# 14_HD4_PUMP.net
KiCad netlist of a schematic drawn in Altium Designer
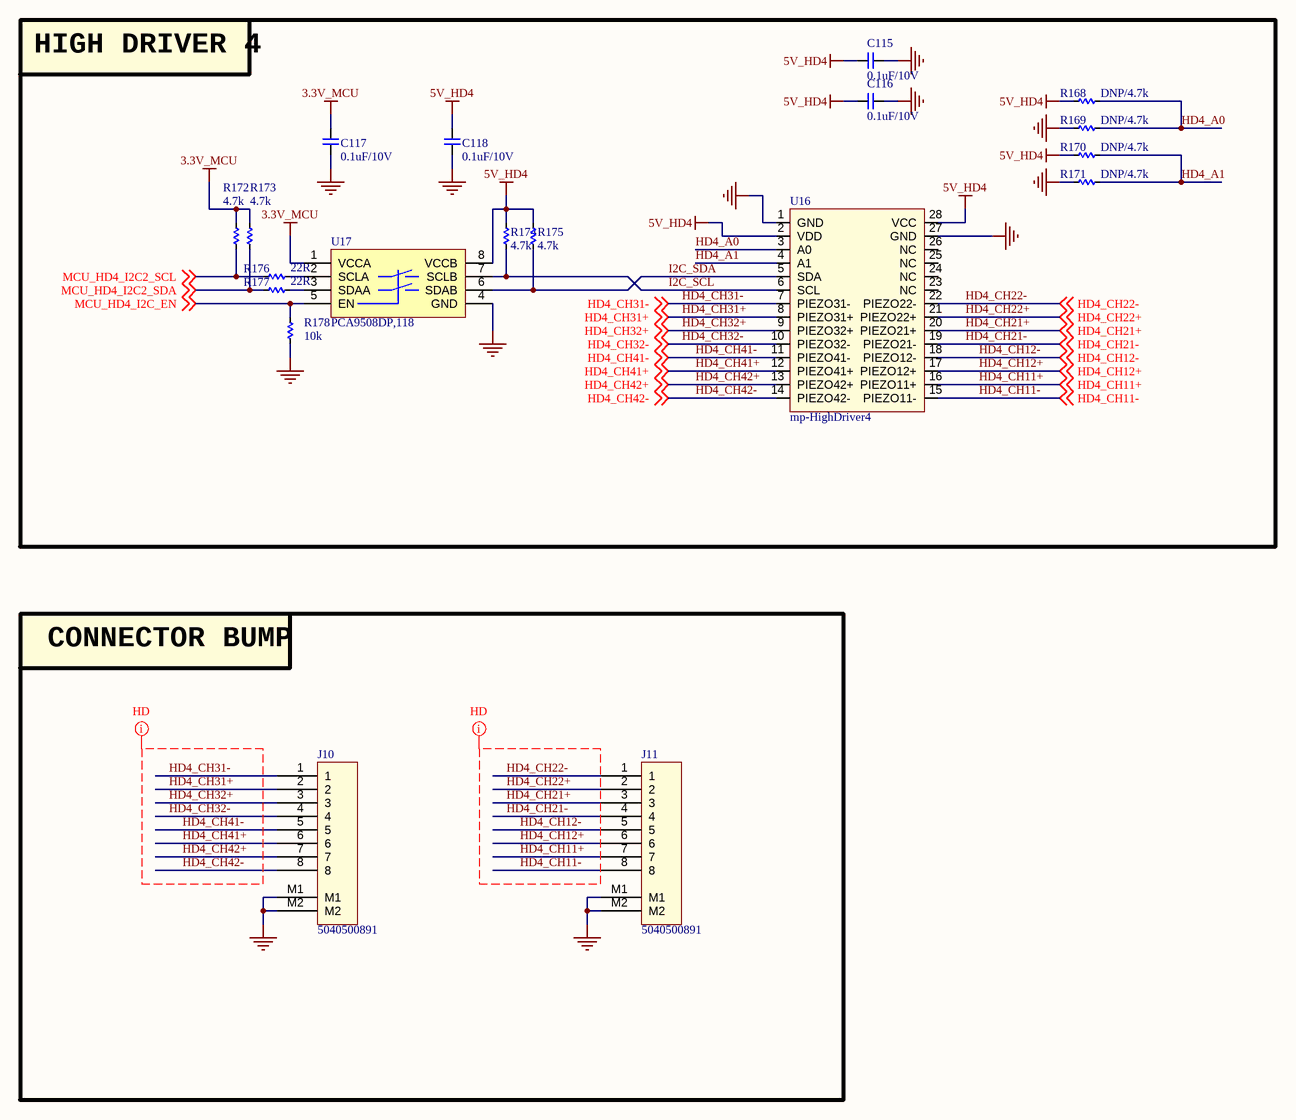
[diagram p0: 14_HD4_PUMP.SchDoc]

(export (version "E")
  (design (tool "Eeschema 10.0.6"))
  (components
    (comp (ref "C115")
      (value "0.1uF/10V")
      (footprint "CAP_C_1005X60")
      (description "CAP CHIP")
      (libsource (lib "LABLIB") (part "_CAP_C_2"))
    )
    (comp (ref "C116")
      (value "0.1uF/10V")
      (footprint "CAP_C_1005X60")
      (description "CAP CHIP")
      (libsource (lib "LABLIB") (part "_CAP_C_2"))
    )
    (comp (ref "C117")
      (value "0.1uF/10V")
      (footprint "CAP_C_1005X60")
      (description "CAP CHIP")
      (libsource (lib "LABLIB") (part "_CAP_C_2"))
    )
    (comp (ref "C118")
      (value "0.1uF/10V")
      (footprint "CAP_C_1005X60")
      (description "CAP CHIP")
      (libsource (lib "LABLIB") (part "_CAP_C_2"))
    )
    (comp (ref "J10")
      (value "5040500891")
      (footprint "MOLEX_5040500891")
      (libsource (lib "LABLIB") (part "Header 8x1_2M"))
    )
    (comp (ref "J11")
      (value "5040500891")
      (footprint "MOLEX_5040500891")
      (libsource (lib "LABLIB") (part "Header 8x1_2M"))
    )
    (comp (ref "R168")
      (value "DNP/4.7k")
      (footprint "RES_C_1005X40")
      (description "RES")
      (libsource (lib "LABLIB") (part "_RES_B_2"))
    )
    (comp (ref "R169")
      (value "DNP/4.7k")
      (footprint "RES_C_1005X40")
      (description "RES")
      (libsource (lib "LABLIB") (part "_RES_B_2"))
    )
    (comp (ref "R170")
      (value "DNP/4.7k")
      (footprint "RES_C_1005X40")
      (description "RES")
      (libsource (lib "LABLIB") (part "_RES_B_2"))
    )
    (comp (ref "R171")
      (value "DNP/4.7k")
      (footprint "RES_C_1005X40")
      (description "RES")
      (libsource (lib "LABLIB") (part "_RES_B_2"))
    )
    (comp (ref "R172")
      (value "4.7k")
      (footprint "RES_C_1005X40")
      (description "RES")
      (libsource (lib "LABLIB") (part "_RES_B_2"))
    )
    (comp (ref "R173")
      (value "4.7k")
      (footprint "RES_C_1005X40")
      (description "RES")
      (libsource (lib "LABLIB") (part "_RES_B_2"))
    )
    (comp (ref "R174")
      (value "4.7k")
      (footprint "RES_C_1005X40")
      (description "RES")
      (libsource (lib "LABLIB") (part "_RES_B_2"))
    )
    (comp (ref "R175")
      (value "4.7k")
      (footprint "RES_C_1005X40")
      (description "RES")
      (libsource (lib "LABLIB") (part "_RES_B_2"))
    )
    (comp (ref "R176")
      (value "22R")
      (footprint "RES_C_1005X40")
      (description "RES")
      (libsource (lib "LABLIB") (part "_RES_B_2"))
    )
    (comp (ref "R177")
      (value "22R")
      (footprint "RES_C_1005X40")
      (description "RES")
      (libsource (lib "LABLIB") (part "_RES_B_2"))
    )
    (comp (ref "R178")
      (value "10k")
      (footprint "RES_C_1005X40")
      (description "RES")
      (libsource (lib "LABLIB") (part "_RES_B_2"))
    )
    (comp (ref "U16")
      (value "mp-HighDriver4")
      (footprint "MP_HIGHDRIVER4")
      (libsource (lib "new_component") (part "mp_HighDriver4"))
    )
    (comp (ref "U17")
      (value "PCA9508DP,118")
      (footprint "TSOP8")
      (libsource (lib "EXP_HW_V3") (part "PCA9508DP,118"))
    )
  )
  (nets
    (net (code "1") (name "/HD4_A0") (class "Default")
      (node (ref "R168") (pin "2") (pinfunction "2_2") (pintype "passive"))
      (node (ref "R169") (pin "2") (pinfunction "2_2") (pintype "passive"))
      (node (ref "U16") (pin "3") (pinfunction "A0_3") (pintype "passive"))
    )
    (net (code "2") (name "/HD4_A1") (class "Default")
      (node (ref "R170") (pin "2") (pinfunction "2_2") (pintype "passive"))
      (node (ref "R171") (pin "2") (pinfunction "2_2") (pintype "passive"))
      (node (ref "U16") (pin "4") (pinfunction "A1_4") (pintype "passive"))
    )
    (net (code "3") (name "/I2C_SCL") (class "Default")
      (node (ref "R174") (pin "2") (pinfunction "2_2") (pintype "passive"))
      (node (ref "U16") (pin "6") (pinfunction "SCL_6") (pintype "passive"))
      (node (ref "U17") (pin "7") (pinfunction "SCLB_7") (pintype "passive"))
    )
    (net (code "4") (name "/I2C_SDA") (class "Default")
      (node (ref "R175") (pin "2") (pinfunction "2_2") (pintype "passive"))
      (node (ref "U16") (pin "5") (pinfunction "SDA_5") (pintype "passive"))
      (node (ref "U17") (pin "6") (pinfunction "SDAB_6") (pintype "passive"))
    )
    (net (code "5") (name "3.3V_MCU") (class "Default")
      (node (ref "C117") (pin "2") (pinfunction "2_2") (pintype "passive"))
      (node (ref "R172") (pin "1") (pinfunction "1_1") (pintype "passive"))
      (node (ref "R173") (pin "1") (pinfunction "1_1") (pintype "passive"))
      (node (ref "U17") (pin "1") (pinfunction "VCCA_1") (pintype "passive"))
    )
    (net (code "6") (name "5V_HD4") (class "Default")
      (node (ref "C115") (pin "2") (pinfunction "2_2") (pintype "passive"))
      (node (ref "C116") (pin "2") (pinfunction "2_2") (pintype "passive"))
      (node (ref "C118") (pin "2") (pinfunction "2_2") (pintype "passive"))
      (node (ref "R168") (pin "1") (pinfunction "1_1") (pintype "passive"))
      (node (ref "R170") (pin "1") (pinfunction "1_1") (pintype "passive"))
      (node (ref "R174") (pin "1") (pinfunction "1_1") (pintype "passive"))
      (node (ref "R175") (pin "1") (pinfunction "1_1") (pintype "passive"))
      (node (ref "U16") (pin "2") (pinfunction "VDD_2") (pintype "power_in"))
      (node (ref "U16") (pin "28") (pinfunction "VCC_28") (pintype "power_in"))
      (node (ref "U17") (pin "8") (pinfunction "VCCB_8") (pintype "passive"))
    )
    (net (code "7") (name "GND") (class "Default")
      (node (ref "C115") (pin "1") (pinfunction "1_1") (pintype "passive"))
      (node (ref "C116") (pin "1") (pinfunction "1_1") (pintype "passive"))
      (node (ref "C117") (pin "1") (pinfunction "1_1") (pintype "passive"))
      (node (ref "C118") (pin "1") (pinfunction "1_1") (pintype "passive"))
      (node (ref "J10") (pin "M1") (pinfunction "M1_M1") (pintype "passive"))
      (node (ref "J10") (pin "M2") (pinfunction "M2_M2") (pintype "passive"))
      (node (ref "J11") (pin "M1") (pinfunction "M1_M1") (pintype "passive"))
      (node (ref "J11") (pin "M2") (pinfunction "M2_M2") (pintype "passive"))
      (node (ref "R169") (pin "1") (pinfunction "1_1") (pintype "passive"))
      (node (ref "R171") (pin "1") (pinfunction "1_1") (pintype "passive"))
      (node (ref "R178") (pin "2") (pinfunction "2_2") (pintype "passive"))
      (node (ref "U16") (pin "1") (pinfunction "GND_1") (pintype "power_in"))
      (node (ref "U16") (pin "27") (pinfunction "GND_27") (pintype "power_in"))
      (node (ref "U17") (pin "4") (pinfunction "GND_4") (pintype "passive"))
    )
    (net (code "8") (name "HD4_CH11+") (class "Default")
      (node (ref "J11") (pin "7") (pinfunction "7_7") (pintype "passive"))
      (node (ref "U16") (pin "16") (pinfunction "PIEZO11+_16") (pintype "passive"))
    )
    (net (code "9") (name "HD4_CH11-") (class "Default")
      (node (ref "J11") (pin "8") (pinfunction "8_8") (pintype "passive"))
      (node (ref "U16") (pin "15") (pinfunction "PIEZO11-_15") (pintype "passive"))
    )
    (net (code "10") (name "HD4_CH12+") (class "Default")
      (node (ref "J11") (pin "6") (pinfunction "6_6") (pintype "passive"))
      (node (ref "U16") (pin "17") (pinfunction "PIEZO12+_17") (pintype "passive"))
    )
    (net (code "11") (name "HD4_CH12-") (class "Default")
      (node (ref "J11") (pin "5") (pinfunction "5_5") (pintype "passive"))
      (node (ref "U16") (pin "18") (pinfunction "PIEZO12-_18") (pintype "passive"))
    )
    (net (code "12") (name "HD4_CH21+") (class "Default")
      (node (ref "J11") (pin "3") (pinfunction "3_3") (pintype "passive"))
      (node (ref "U16") (pin "20") (pinfunction "PIEZO21+_20") (pintype "passive"))
    )
    (net (code "13") (name "HD4_CH21-") (class "Default")
      (node (ref "J11") (pin "4") (pinfunction "4_4") (pintype "passive"))
      (node (ref "U16") (pin "19") (pinfunction "PIEZO21-_19") (pintype "passive"))
    )
    (net (code "14") (name "HD4_CH22+") (class "Default")
      (node (ref "J11") (pin "2") (pinfunction "2_2") (pintype "passive"))
      (node (ref "U16") (pin "21") (pinfunction "PIEZO22+_21") (pintype "passive"))
    )
    (net (code "15") (name "HD4_CH22-") (class "Default")
      (node (ref "J11") (pin "1") (pinfunction "1_1") (pintype "passive"))
      (node (ref "U16") (pin "22") (pinfunction "PIEZO22-_22") (pintype "passive"))
    )
    (net (code "16") (name "HD4_CH31+") (class "Default")
      (node (ref "J10") (pin "2") (pinfunction "2_2") (pintype "passive"))
      (node (ref "U16") (pin "8") (pinfunction "PIEZO31+_8") (pintype "passive"))
    )
    (net (code "17") (name "HD4_CH31-") (class "Default")
      (node (ref "J10") (pin "1") (pinfunction "1_1") (pintype "passive"))
      (node (ref "U16") (pin "7") (pinfunction "PIEZO31-_7") (pintype "passive"))
    )
    (net (code "18") (name "HD4_CH32+") (class "Default")
      (node (ref "J10") (pin "3") (pinfunction "3_3") (pintype "passive"))
      (node (ref "U16") (pin "9") (pinfunction "PIEZO32+_9") (pintype "passive"))
    )
    (net (code "19") (name "HD4_CH32-") (class "Default")
      (node (ref "J10") (pin "4") (pinfunction "4_4") (pintype "passive"))
      (node (ref "U16") (pin "10") (pinfunction "PIEZO32-_10") (pintype "passive"))
    )
    (net (code "20") (name "HD4_CH41+") (class "Default")
      (node (ref "J10") (pin "6") (pinfunction "6_6") (pintype "passive"))
      (node (ref "U16") (pin "12") (pinfunction "PIEZO41+_12") (pintype "passive"))
    )
    (net (code "21") (name "HD4_CH41-") (class "Default")
      (node (ref "J10") (pin "5") (pinfunction "5_5") (pintype "passive"))
      (node (ref "U16") (pin "11") (pinfunction "PIEZO41-_11") (pintype "passive"))
    )
    (net (code "22") (name "HD4_CH42+") (class "Default")
      (node (ref "J10") (pin "7") (pinfunction "7_7") (pintype "passive"))
      (node (ref "U16") (pin "13") (pinfunction "PIEZO42+_13") (pintype "passive"))
    )
    (net (code "23") (name "HD4_CH42-") (class "Default")
      (node (ref "J10") (pin "8") (pinfunction "8_8") (pintype "passive"))
      (node (ref "U16") (pin "14") (pinfunction "PIEZO42-_14") (pintype "passive"))
    )
    (net (code "24") (name "MCU_HD4_I2C2_SCL") (class "Default")
      (node (ref "R172") (pin "2") (pinfunction "2_2") (pintype "passive"))
      (node (ref "R176") (pin "2") (pinfunction "2_2") (pintype "passive"))
    )
    (net (code "25") (name "MCU_HD4_I2C2_SDA") (class "Default")
      (node (ref "R173") (pin "2") (pinfunction "2_2") (pintype "passive"))
      (node (ref "R177") (pin "2") (pinfunction "2_2") (pintype "passive"))
    )
    (net (code "26") (name "MCU_HD4_I2C_EN") (class "Default")
      (node (ref "R178") (pin "1") (pinfunction "1_1") (pintype "passive"))
      (node (ref "U17") (pin "5") (pinfunction "EN_5") (pintype "passive"))
    )
    (net (code "27") (name "Net-(U17-SCLA)") (class "Default")
      (node (ref "R176") (pin "1") (pinfunction "1_1") (pintype "passive"))
      (node (ref "U17") (pin "2") (pinfunction "SCLA_2") (pintype "passive"))
    )
    (net (code "28") (name "Net-(U17-SDAA)") (class "Default")
      (node (ref "R177") (pin "1") (pinfunction "1_1") (pintype "passive"))
      (node (ref "U17") (pin "3") (pinfunction "SDAA_3") (pintype "passive"))
    )
    (net (code "29") (name "unconnected-(U16-NC-Pad23)") (class "Default")
      (node (ref "U16") (pin "23") (pinfunction "NC_23") (pintype "passive"))
    )
    (net (code "30") (name "unconnected-(U16-NC-Pad24)") (class "Default")
      (node (ref "U16") (pin "24") (pinfunction "NC_24") (pintype "passive"))
    )
    (net (code "31") (name "unconnected-(U16-NC-Pad25)") (class "Default")
      (node (ref "U16") (pin "25") (pinfunction "NC_25") (pintype "passive"))
    )
    (net (code "32") (name "unconnected-(U16-NC-Pad26)") (class "Default")
      (node (ref "U16") (pin "26") (pinfunction "NC_26") (pintype "passive"))
    )
  )
)
